# 02_TFT_LED.net
KiCad netlist of a schematic drawn in Altium Designer
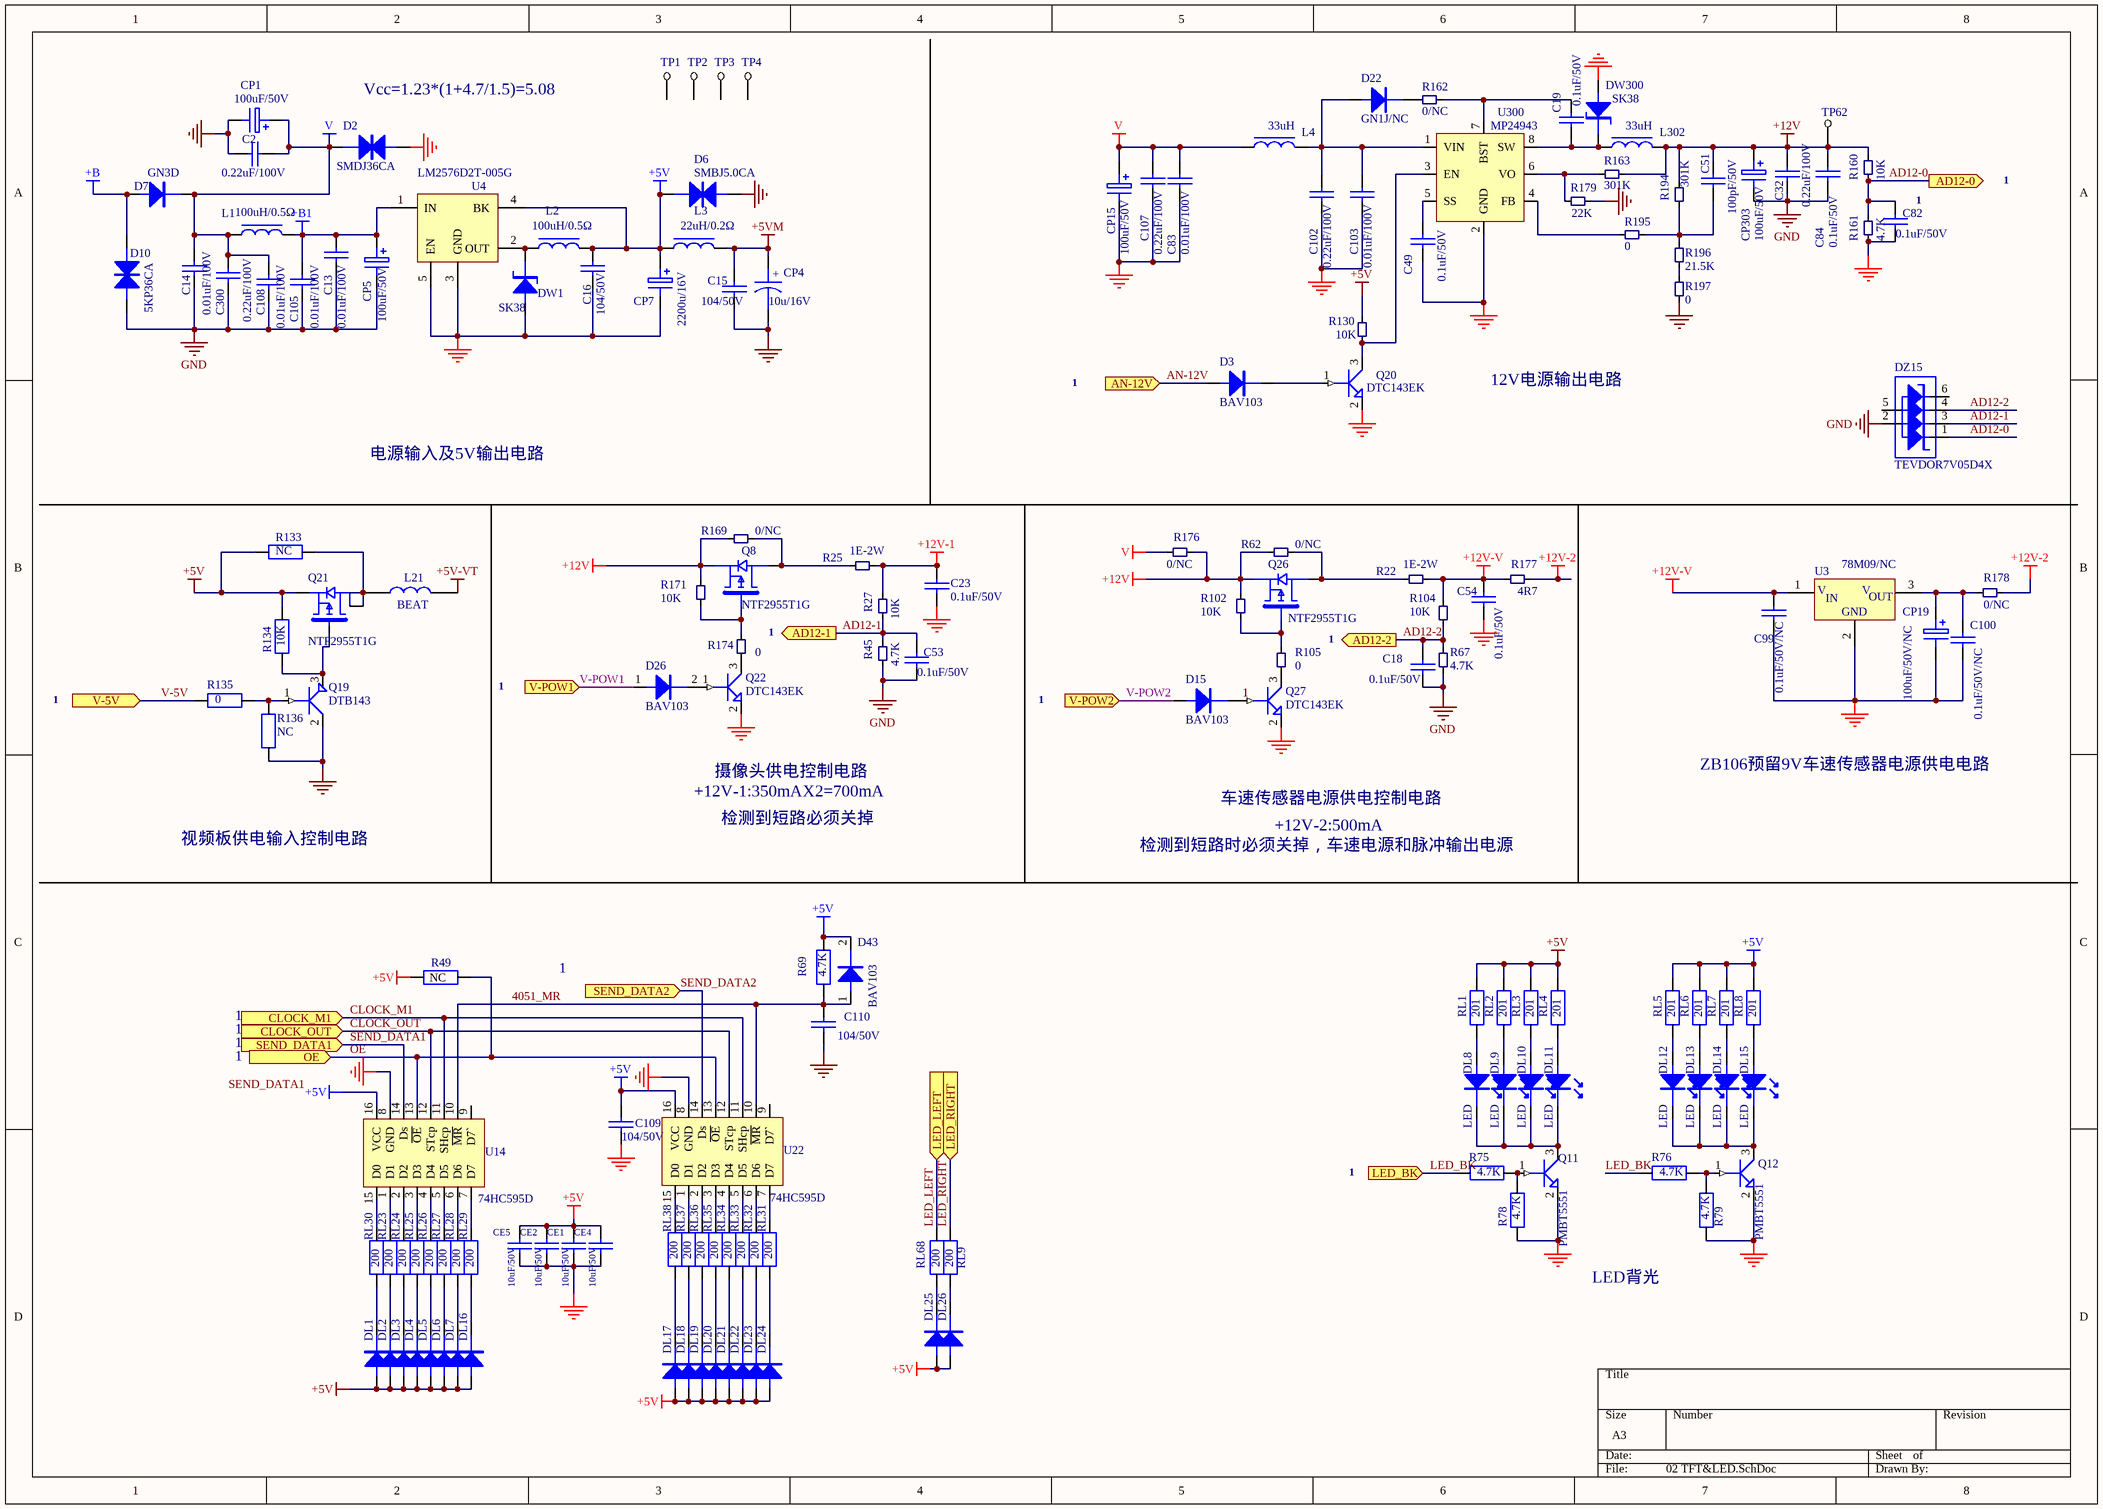
[diagram p0: 02 TFT&LED.SchDoc]

(export (version "E")
  (design (tool "Eeschema 10.0.6"))
  (components
    (comp (ref "C2")
      (value "0.22uF/100V")
      (footprint "CR1206")
      (description "Capacitor")
      (libsource (lib "*") (part "CAP"))
    )
    (comp (ref "C13")
      (value "0.01uF/100V")
      (footprint "CR0805")
      (description "Capacitor")
      (libsource (lib "*") (part "CAP"))
    )
    (comp (ref "C14")
      (value "0.01uF/100V")
      (footprint "CR0805")
      (description "Capacitor")
      (libsource (lib "*") (part "CAP"))
    )
    (comp (ref "C15")
      (value "104/50V")
      (footprint "CR0805")
      (description "Capacitor")
      (libsource (lib "*") (part "CAP"))
    )
    (comp (ref "C16")
      (value "104/50V")
      (footprint "CR0805")
      (description "Capacitor")
      (libsource (lib "*") (part "CAP"))
    )
    (comp (ref "C18")
      (value "0.1uF/50V")
      (footprint "CR0805")
      (description "Capacitor")
      (libsource (lib "*") (part "CAP"))
    )
    (comp (ref "C19")
      (value "0.1uF/50V")
      (footprint "CR0805")
      (description "Capacitor")
      (libsource (lib "*") (part "CAP"))
    )
    (comp (ref "C23")
      (value "0.1uF/50V")
      (footprint "CR0805")
      (description "Capacitor")
      (libsource (lib "*") (part "CAP"))
    )
    (comp (ref "C32")
      (value "0.22uF/100V")
      (footprint "CR1206")
      (description "Capacitor")
      (libsource (lib "*") (part "CAP"))
    )
    (comp (ref "C49")
      (value "0.1uF/50V")
      (footprint "CR0805")
      (description "Capacitor")
      (libsource (lib "*") (part "CAP"))
    )
    (comp (ref "C51")
      (value "100pF/50V")
      (footprint "CR0805")
      (description "Capacitor")
      (libsource (lib "*") (part "CAP"))
    )
    (comp (ref "C53")
      (value "0.1uF/50V")
      (footprint "CR0805")
      (description "Capacitor")
      (libsource (lib "*") (part "CAP"))
    )
    (comp (ref "C54")
      (value "0.1uF/50V")
      (footprint "CR0805")
      (description "Capacitor")
      (libsource (lib "*") (part "CAP"))
    )
    (comp (ref "C82")
      (value "0.1uF/50V")
      (footprint "CR0805")
      (description "Capacitor")
      (libsource (lib "*") (part "CAP"))
    )
    (comp (ref "C83")
      (value "0.01uF/100V")
      (footprint "CR0805")
      (description "Capacitor")
      (libsource (lib "*") (part "CAP"))
    )
    (comp (ref "C84")
      (value "0.1uF/50V")
      (footprint "CR0805")
      (description "Capacitor")
      (libsource (lib "*") (part "CAP"))
    )
    (comp (ref "C99")
      (value "0.1uF/50V/NC")
      (footprint "CR0805")
      (description "Capacitor")
      (libsource (lib "*") (part "CAP"))
    )
    (comp (ref "C100")
      (value "0.1uF/50V/NC")
      (footprint "CR0805")
      (description "Capacitor")
      (libsource (lib "*") (part "CAP"))
    )
    (comp (ref "C102")
      (value "0.22uF/100V")
      (footprint "CR1206")
      (description "Capacitor")
      (libsource (lib "*") (part "CAP"))
    )
    (comp (ref "C103")
      (value "0.01uF/100V")
      (footprint "CR0805")
      (description "Capacitor")
      (libsource (lib "*") (part "CAP"))
    )
    (comp (ref "C105")
      (value "0.01uF/100V")
      (footprint "CR0805")
      (description "Capacitor")
      (libsource (lib "*") (part "CAP"))
    )
    (comp (ref "C107")
      (value "0.22uF/100V")
      (footprint "CR1206")
      (description "Capacitor")
      (libsource (lib "*") (part "CAP"))
    )
    (comp (ref "C108")
      (value "0.01uF/100V")
      (footprint "CR0805")
      (description "Capacitor")
      (libsource (lib "*") (part "CAP"))
    )
    (comp (ref "C109")
      (value "104/50V")
      (footprint "CR0805")
      (description "Capacitor")
      (libsource (lib "*") (part "CAP"))
    )
    (comp (ref "C110")
      (value "104/50V")
      (footprint "CR0805")
      (description "Capacitor")
      (libsource (lib "*") (part "CAP"))
    )
    (comp (ref "C300")
      (value "0.22uF/100V")
      (footprint "CR1206")
      (description "Capacitor")
      (libsource (lib "*") (part "CAP"))
    )
    (comp (ref "CE1")
      (value "10uF/50V")
      (footprint "CR1206")
      (description "Capacitor")
      (libsource (lib "*") (part "CAP"))
    )
    (comp (ref "CE2")
      (value "10uF/50V")
      (footprint "CR1206")
      (description "Capacitor")
      (libsource (lib "*") (part "CAP"))
    )
    (comp (ref "CE4")
      (value "10uF/50V")
      (footprint "CR1206")
      (description "Capacitor")
      (libsource (lib "*") (part "CAP"))
    )
    (comp (ref "CE5")
      (value "10uF/50V")
      (footprint "CR1206")
      (description "Capacitor")
      (libsource (lib "*") (part "CAP"))
    )
    (comp (ref "CP1")
      (value "100uF/50V")
      (footprint "RB10")
      (description "电解电容")
      (libsource (lib "*") (part "ELECTRO1"))
    )
    (comp (ref "CP4")
      (value "10u/16V")
      (footprint "CE1206")
      (description "Capacitor")
      (libsource (lib "*") (part "CAPACITOR POL"))
    )
    (comp (ref "CP5")
      (value "100uF/50V")
      (footprint "RB5-1")
      (description "电解电容")
      (libsource (lib "*") (part "ELECTRO1"))
    )
    (comp (ref "CP7")
      (value "2200u/16V")
      (footprint "RB12.5")
      (description "电解电容")
      (libsource (lib "*") (part "ELECTRO1"))
    )
    (comp (ref "CP15")
      (value "100uF/50V")
      (footprint "RB5-1")
      (description "电解电容")
      (libsource (lib "*") (part "ELECTRO1"))
    )
    (comp (ref "CP19")
      (value "100uF/50V/NC")
      (footprint "RB5-1")
      (description "电解电容")
      (libsource (lib "*") (part "ELECTRO1"))
    )
    (comp (ref "CP303")
      (value "100uF/50V")
      (footprint "RB5-1")
      (description "电解电容")
      (libsource (lib "*") (part "ELECTRO1"))
    )
    (comp (ref "D2") (value "SMDJ36CA") (footprint "SMC-D") (libsource (lib "YDM-SQ-1SCH") (part "TVS")))
    (comp (ref "D3")
      (value "BAV103")
      (footprint "SOD-80C")
      (description "二极管")
      (libsource (lib "") (part "DIODE_1"))
    )
    (comp (ref "D6") (value "SMBJ5.0CA") (footprint "SMB-D") (libsource (lib "YDM-SQ-1SCH") (part "TVS")))
    (comp (ref "D7")
      (value "GN3D")
      (footprint "SMC")
      (description "二极管")
      (libsource (lib "") (part "DIODE_1"))
    )
    (comp (ref "D10") (value "5KP36CA") (footprint "D-17") (libsource (lib "*") (part "TVS")))
    (comp (ref "D15")
      (value "BAV103")
      (footprint "SOD-80C")
      (description "二极管")
      (libsource (lib "") (part "DIODE_1"))
    )
    (comp (ref "D22")
      (value "GN1J/NC")
      (footprint "SMA")
      (description "二极管")
      (libsource (lib "") (part "DIODE_1"))
    )
    (comp (ref "D26")
      (value "BAV103")
      (footprint "SOD-80C")
      (description "二极管")
      (libsource (lib "*") (part "DIODE"))
    )
    (comp (ref "D43")
      (value "BAV103")
      (footprint "SOD-80C")
      (description "二极管")
      (libsource (lib "*") (part "DIODE"))
    )
    (comp (ref "DL1")
      (value "~")
      (footprint "LED1210")
      (description "贴片二极管")
      (libsource (lib "*") (part "DOS"))
    )
    (comp (ref "DL2")
      (value "~")
      (footprint "LED1210")
      (description "贴片二极管")
      (libsource (lib "*") (part "DOS"))
    )
    (comp (ref "DL3")
      (value "~")
      (footprint "LED1210")
      (description "贴片二极管")
      (libsource (lib "*") (part "DOS"))
    )
    (comp (ref "DL4")
      (value "~")
      (footprint "LED1210")
      (description "贴片二极管")
      (libsource (lib "*") (part "DOS"))
    )
    (comp (ref "DL5")
      (value "~")
      (footprint "LED1210")
      (description "贴片二极管")
      (libsource (lib "*") (part "DOS"))
    )
    (comp (ref "DL6")
      (value "~")
      (footprint "LED1210")
      (description "贴片二极管")
      (libsource (lib "*") (part "DOS"))
    )
    (comp (ref "DL7")
      (value "~")
      (footprint "LED1210")
      (description "贴片二极管")
      (libsource (lib "*") (part "DOS"))
    )
    (comp (ref "DL8")
      (value "LED")
      (footprint "LED1210")
      (description "贴片LED")
      (libsource (lib "*") (part "LED"))
    )
    (comp (ref "DL9")
      (value "LED")
      (footprint "LED1210")
      (description "贴片LED")
      (libsource (lib "*") (part "LED"))
    )
    (comp (ref "DL10")
      (value "LED")
      (footprint "LED1210")
      (description "贴片LED")
      (libsource (lib "*") (part "LED"))
    )
    (comp (ref "DL11")
      (value "LED")
      (footprint "LED1210")
      (description "贴片LED")
      (libsource (lib "*") (part "LED"))
    )
    (comp (ref "DL12")
      (value "LED")
      (footprint "LED1210")
      (description "贴片LED")
      (libsource (lib "*") (part "LED"))
    )
    (comp (ref "DL13")
      (value "LED")
      (footprint "LED1210")
      (description "贴片LED")
      (libsource (lib "*") (part "LED"))
    )
    (comp (ref "DL14")
      (value "LED")
      (footprint "LED1210")
      (description "贴片LED")
      (libsource (lib "*") (part "LED"))
    )
    (comp (ref "DL15")
      (value "LED")
      (footprint "LED1210")
      (description "贴片LED")
      (libsource (lib "*") (part "LED"))
    )
    (comp (ref "DL16")
      (value "~")
      (footprint "LED1210")
      (description "贴片二极管")
      (libsource (lib "*") (part "DOS"))
    )
    (comp (ref "DL17")
      (value "~")
      (footprint "LED1210")
      (description "贴片二极管")
      (libsource (lib "*") (part "DOS"))
    )
    (comp (ref "DL18")
      (value "~")
      (footprint "LED1210")
      (description "贴片二极管")
      (libsource (lib "*") (part "DOS"))
    )
    (comp (ref "DL19")
      (value "~")
      (footprint "LED1210")
      (description "贴片二极管")
      (libsource (lib "*") (part "DOS"))
    )
    (comp (ref "DL20")
      (value "~")
      (footprint "LED1210")
      (description "贴片二极管")
      (libsource (lib "*") (part "DOS"))
    )
    (comp (ref "DL21")
      (value "~")
      (footprint "LED1210")
      (description "贴片二极管")
      (libsource (lib "*") (part "DOS"))
    )
    (comp (ref "DL22")
      (value "~")
      (footprint "LED1210")
      (description "贴片二极管")
      (libsource (lib "*") (part "DOS"))
    )
    (comp (ref "DL23")
      (value "~")
      (footprint "LED1210")
      (description "贴片二极管")
      (libsource (lib "*") (part "DOS"))
    )
    (comp (ref "DL24")
      (value "~")
      (footprint "LED1210")
      (description "贴片二极管")
      (libsource (lib "*") (part "DOS"))
    )
    (comp (ref "DL25")
      (value "~")
      (footprint "LED1210")
      (description "贴片二极管")
      (libsource (lib "*") (part "DOS"))
    )
    (comp (ref "DL26")
      (value "~")
      (footprint "LED1210")
      (description "贴片二极管")
      (libsource (lib "*") (part "DOS"))
    )
    (comp (ref "DW1")
      (value "SK38")
      (footprint "SMC")
      (description "稳压二极管")
      (libsource (lib "*") (part "DW"))
    )
    (comp (ref "DW300")
      (value "SK38")
      (footprint "SMC")
      (description "稳压二极管")
      (libsource (lib "*") (part "DW"))
    )
    (comp (ref "DZ15")
      (value "TEVDOR7V05D4X")
      (footprint "SOT-457")
      (description "二极管排")
      (libsource (lib "yibiaoschlib") (part "TEVDOR7V05D4X"))
    )
    (comp (ref "L1")
      (value "100uH/0.5Ω")
      (footprint "Ind-R13-7-100")
      (description "电感")
      (libsource (lib "*") (part "L"))
    )
    (comp (ref "L2")
      (value "100uH/0.5Ω")
      (footprint "Ind-R13-7-100")
      (description "电感")
      (libsource (lib "*") (part "L"))
    )
    (comp (ref "L3")
      (value "22uH/0.2Ω")
      (footprint "SS0603")
      (description "SS0603220ML")
      (libsource (lib "*") (part "L"))
    )
    (comp (ref "L4")
      (value "33uH")
      (footprint "Ind-R13-7-100")
      (description "电感")
      (libsource (lib "*") (part "L"))
    )
    (comp (ref "L21") (value "BEAT") (footprint "CR0805") (libsource (lib "YDM-SQ-1SCH") (part "BEAT")))
    (comp (ref "L302")
      (value "33uH")
      (footprint "Ind-R13-7-100")
      (description "电感")
      (libsource (lib "*") (part "L"))
    )
    (comp (ref "Q8")
      (value "NTF2955T1G")
      (footprint "SOT-223")
      (description "MOS")
      (libsource (lib "Ô­ÀíÍ¼¿â-1SCH") (part "MOS-P"))
    )
    (comp (ref "Q11")
      (value "PMBT5551")
      (footprint "SOT23")
      (description "PNP   三极管")
      (libsource (lib "Ô­ÀíÍ¼¿â-1SCH") (part "PMBT5551"))
    )
    (comp (ref "Q12")
      (value "PMBT5551")
      (footprint "SOT23")
      (description "PNP   三极管")
      (libsource (lib "Ô­ÀíÍ¼¿â-1SCH") (part "PMBT5551"))
    )
    (comp (ref "Q19") (value "DTB143") (footprint "SOT23") (libsource (lib "Ô­ÀíÍ¼¿â-1SCH") (part "BCX53")))
    (comp (ref "Q20")
      (value "DTC143EK")
      (footprint "SOT23")
      (description "NPN")
      (libsource (lib "Ô­ÀíÍ¼¿â-1SCH") (part "DTC143"))
    )
    (comp (ref "Q21")
      (value "NTF2955T1G")
      (footprint "SOT-223")
      (description "MOS")
      (libsource (lib "yibiaoschlib") (part "NTF2955T1G"))
    )
    (comp (ref "Q22")
      (value "DTC143EK")
      (footprint "SOT23")
      (description "NPN")
      (libsource (lib "Ô­ÀíÍ¼¿â-1SCH") (part "DTC143"))
    )
    (comp (ref "Q26")
      (value "NTF2955T1G")
      (footprint "SOT-223")
      (description "MOS")
      (libsource (lib "Ô­ÀíÍ¼¿â-1SCH") (part "MOS-P"))
    )
    (comp (ref "Q27")
      (value "DTC143EK")
      (footprint "SOT23")
      (description "NPN")
      (libsource (lib "Ô­ÀíÍ¼¿â-1SCH") (part "DTC143"))
    )
    (comp (ref "R22")
      (value "1E-2W")
      (footprint "R2512")
      (description "贴片电阻")
      (libsource (lib "YDM-SQ-1SCH") (part "Resister mini"))
    )
    (comp (ref "R25")
      (value "1E-2W")
      (footprint "R2512")
      (description "贴片电阻")
      (libsource (lib "YDM-SQ-1SCH") (part "Resister mini"))
    )
    (comp (ref "R27")
      (value "10K")
      (footprint "CR0805")
      (description "贴片电阻")
      (libsource (lib "YDM-SQ-1SCH") (part "Resister mini"))
    )
    (comp (ref "R45")
      (value "4.7K")
      (footprint "CR0805")
      (description "贴片电阻")
      (libsource (lib "YDM-SQ-1SCH") (part "Resister mini"))
    )
    (comp (ref "R49")
      (value "NC")
      (footprint "CR0805")
      (description "贴片电阻")
      (libsource (lib "*") (part "RES"))
    )
    (comp (ref "R62")
      (value "0/NC")
      (footprint "CR1206")
      (description "贴片电阻")
      (libsource (lib "YDM-SQ-1SCH") (part "Resister mini"))
    )
    (comp (ref "R67")
      (value "4.7K")
      (footprint "CR0805")
      (description "贴片电阻")
      (libsource (lib "YDM-SQ-1SCH") (part "Resister mini"))
    )
    (comp (ref "R69")
      (value "4.7K")
      (footprint "CR0805")
      (description "贴片电阻")
      (libsource (lib "*") (part "RES"))
    )
    (comp (ref "R75")
      (value "4.7K")
      (footprint "CR0805")
      (description "贴片电阻")
      (libsource (lib "YDM-SQ-1SCH") (part "RES"))
    )
    (comp (ref "R76")
      (value "4.7K")
      (footprint "CR0805")
      (description "贴片电阻")
      (libsource (lib "YDM-SQ-1SCH") (part "RES"))
    )
    (comp (ref "R78")
      (value "4.7K")
      (footprint "CR0805")
      (description "贴片电阻")
      (libsource (lib "YDM-SQ-1SCH") (part "RES"))
    )
    (comp (ref "R79")
      (value "4.7K")
      (footprint "CR0805")
      (description "贴片电阻")
      (libsource (lib "YDM-SQ-1SCH") (part "RES"))
    )
    (comp (ref "R102")
      (value "10K")
      (footprint "CR0805")
      (description "贴片电阻")
      (libsource (lib "YDM-SQ-1SCH") (part "Resister mini"))
    )
    (comp (ref "R104")
      (value "10K")
      (footprint "CR0805")
      (description "贴片电阻")
      (libsource (lib "YDM-SQ-1SCH") (part "Resister mini"))
    )
    (comp (ref "R105")
      (value "0")
      (footprint "CR0805")
      (description "贴片电阻")
      (libsource (lib "YDM-SQ-1SCH") (part "Resister mini"))
    )
    (comp (ref "R130")
      (value "10K")
      (footprint "CR0805")
      (description "贴片电阻")
      (libsource (lib "YDM-SQ-1SCH") (part "Resister mini"))
    )
    (comp (ref "R133")
      (value "NC")
      (footprint "CR1206")
      (description "贴片电阻")
      (libsource (lib "YDM-SQ-1SCH") (part "RES"))
    )
    (comp (ref "R134")
      (value "10K")
      (footprint "CR0805")
      (description "贴片电阻")
      (libsource (lib "YDM-SQ-1SCH") (part "RES"))
    )
    (comp (ref "R135")
      (value "0")
      (footprint "CR0805")
      (description "贴片电阻")
      (libsource (lib "YDM-SQ-1SCH") (part "RES"))
    )
    (comp (ref "R136")
      (value "NC")
      (footprint "CR0805")
      (description "贴片电阻")
      (libsource (lib "YDM-SQ-1SCH") (part "RES"))
    )
    (comp (ref "R160")
      (value "10K")
      (footprint "CR0805")
      (description "贴片电阻")
      (libsource (lib "YDM-SQ-1SCH") (part "Resister mini"))
    )
    (comp (ref "R161")
      (value "4.7K")
      (footprint "CR0805")
      (description "贴片电阻")
      (libsource (lib "YDM-SQ-1SCH") (part "Resister mini"))
    )
    (comp (ref "R162")
      (value "0/NC")
      (footprint "CR0805")
      (description "贴片电阻")
      (libsource (lib "YDM-SQ-1SCH") (part "Resister mini"))
    )
    (comp (ref "R163")
      (value "301K")
      (footprint "CR0805")
      (description "贴片电阻")
      (libsource (lib "YDM-SQ-1SCH") (part "Resister mini"))
    )
    (comp (ref "R169")
      (value "0/NC")
      (footprint "CR1206")
      (description "贴片电阻")
      (libsource (lib "YDM-SQ-1SCH") (part "Resister mini"))
    )
    (comp (ref "R171")
      (value "10K")
      (footprint "CR0805")
      (description "贴片电阻")
      (libsource (lib "YDM-SQ-1SCH") (part "Resister mini"))
    )
    (comp (ref "R174")
      (value "0")
      (footprint "CR0805")
      (description "贴片电阻")
      (libsource (lib "YDM-SQ-1SCH") (part "Resister mini"))
    )
    (comp (ref "R176")
      (value "0/NC")
      (footprint "CR1206")
      (description "贴片电阻")
      (libsource (lib "YDM-SQ-1SCH") (part "Resister mini"))
    )
    (comp (ref "R177")
      (value "4R7")
      (footprint "CR1206")
      (description "贴片电阻")
      (libsource (lib "YDM-SQ-1SCH") (part "Resister mini"))
    )
    (comp (ref "R178")
      (value "0/NC")
      (footprint "CR1206")
      (description "贴片电阻")
      (libsource (lib "YDM-SQ-1SCH") (part "Resister mini"))
    )
    (comp (ref "R179")
      (value "22K")
      (footprint "CR0805")
      (description "贴片电阻")
      (libsource (lib "YDM-SQ-1SCH") (part "Resister mini"))
    )
    (comp (ref "R194")
      (value "301K")
      (footprint "CR0805")
      (description "贴片电阻")
      (libsource (lib "YDM-SQ-1SCH") (part "Resister mini"))
    )
    (comp (ref "R195")
      (value "0")
      (footprint "CR0805")
      (description "贴片电阻")
      (libsource (lib "YDM-SQ-1SCH") (part "Resister mini"))
    )
    (comp (ref "R196")
      (value "21.5K")
      (footprint "CR0805")
      (description "贴片电阻")
      (libsource (lib "YDM-SQ-1SCH") (part "Resister mini"))
    )
    (comp (ref "R197")
      (value "0")
      (footprint "CR0805")
      (description "贴片电阻")
      (libsource (lib "YDM-SQ-1SCH") (part "Resister mini"))
    )
    (comp (ref "RL1")
      (value "201")
      (footprint "CR0805")
      (description "贴片电阻")
      (libsource (lib "*") (part "RES"))
    )
    (comp (ref "RL2")
      (value "201")
      (footprint "CR0805")
      (description "贴片电阻")
      (libsource (lib "*") (part "RES"))
    )
    (comp (ref "RL3")
      (value "201")
      (footprint "CR0805")
      (description "贴片电阻")
      (libsource (lib "*") (part "RES"))
    )
    (comp (ref "RL4")
      (value "201")
      (footprint "CR0805")
      (description "贴片电阻")
      (libsource (lib "*") (part "RES"))
    )
    (comp (ref "RL5")
      (value "201")
      (footprint "CR0805")
      (description "贴片电阻")
      (libsource (lib "*") (part "RES"))
    )
    (comp (ref "RL6")
      (value "201")
      (footprint "CR0805")
      (description "贴片电阻")
      (libsource (lib "*") (part "RES"))
    )
    (comp (ref "RL7")
      (value "201")
      (footprint "CR0805")
      (description "贴片电阻")
      (libsource (lib "*") (part "RES"))
    )
    (comp (ref "RL8")
      (value "201")
      (footprint "CR0805")
      (description "贴片电阻")
      (libsource (lib "*") (part "RES"))
    )
    (comp (ref "RL9")
      (value "200")
      (footprint "CR0805")
      (description "贴片电阻")
      (libsource (lib "*") (part "RES"))
    )
    (comp (ref "RL23")
      (value "200")
      (footprint "CR0805")
      (description "贴片电阻")
      (libsource (lib "*") (part "RES"))
    )
    (comp (ref "RL24")
      (value "200")
      (footprint "CR0805")
      (description "贴片电阻")
      (libsource (lib "*") (part "RES"))
    )
    (comp (ref "RL25")
      (value "200")
      (footprint "CR0805")
      (description "贴片电阻")
      (libsource (lib "*") (part "RES"))
    )
    (comp (ref "RL26")
      (value "200")
      (footprint "CR0805")
      (description "贴片电阻")
      (libsource (lib "*") (part "RES"))
    )
    (comp (ref "RL27")
      (value "200")
      (footprint "CR0805")
      (description "贴片电阻")
      (libsource (lib "*") (part "RES"))
    )
    (comp (ref "RL28")
      (value "200")
      (footprint "CR0805")
      (description "贴片电阻")
      (libsource (lib "*") (part "RES"))
    )
    (comp (ref "RL29")
      (value "200")
      (footprint "CR0805")
      (description "贴片电阻")
      (libsource (lib "*") (part "RES"))
    )
    (comp (ref "RL30")
      (value "200")
      (footprint "CR0805")
      (description "贴片电阻")
      (libsource (lib "*") (part "RES"))
    )
    (comp (ref "RL31")
      (value "200")
      (footprint "CR0805")
      (description "贴片电阻")
      (libsource (lib "*") (part "RES"))
    )
    (comp (ref "RL32")
      (value "200")
      (footprint "CR0805")
      (description "贴片电阻")
      (libsource (lib "*") (part "RES"))
    )
    (comp (ref "RL33")
      (value "200")
      (footprint "CR0805")
      (description "贴片电阻")
      (libsource (lib "*") (part "RES"))
    )
    (comp (ref "RL34")
      (value "200")
      (footprint "CR0805")
      (description "贴片电阻")
      (libsource (lib "*") (part "RES"))
    )
    (comp (ref "RL35")
      (value "200")
      (footprint "CR0805")
      (description "贴片电阻")
      (libsource (lib "*") (part "RES"))
    )
    (comp (ref "RL36")
      (value "200")
      (footprint "CR0805")
      (description "贴片电阻")
      (libsource (lib "*") (part "RES"))
    )
    (comp (ref "RL37")
      (value "200")
      (footprint "CR0805")
      (description "贴片电阻")
      (libsource (lib "*") (part "RES"))
    )
    (comp (ref "RL38")
      (value "200")
      (footprint "CR0805")
      (description "贴片电阻")
      (libsource (lib "*") (part "RES"))
    )
    (comp (ref "RL68")
      (value "200")
      (footprint "CR0805")
      (description "贴片电阻")
      (libsource (lib "*") (part "RES"))
    )
    (comp (ref "TP1") (value "TP") (footprint "MARK") (libsource (lib "YDM-SQ-1SCH") (part "TP")))
    (comp (ref "TP2") (value "TP") (footprint "MARK") (libsource (lib "YDM-SQ-1SCH") (part "TP")))
    (comp (ref "TP3") (value "TP") (footprint "MARK") (libsource (lib "YDM-SQ-1SCH") (part "TP")))
    (comp (ref "TP4") (value "TP") (footprint "MARK") (libsource (lib "YDM-SQ-1SCH") (part "TP")))
    (comp (ref "TP62") (value "~") (footprint "TP") (libsource (lib "YDM-SQ-1SCH") (part "TP")))
    (comp (ref "U3")
      (value "78M09/NC")
      (footprint "DPAK")
      (description "IC-三端稳压")
      (libsource (lib "HNS-SCH") (part "78M12"))
    )
    (comp (ref "U4")
      (value "LM2576D2T-005G")
      (footprint "SOT-263-5")
      (description "DC/DC")
      (libsource (lib "*") (part "LDO_1"))
    )
    (comp (ref "U14") (value "74HC595D") (footprint "SO-16") (libsource (lib "*") (part "74HC595D")))
    (comp (ref "U22") (value "74HC595D") (footprint "SO-16") (libsource (lib "*") (part "74HC595D")))
    (comp (ref "U300")
      (value "MP24943")
      (footprint "SOIC8E")
      (description "IC-CAN DRIVER")
      (libsource (lib "Ô­ÀíÍ¼¿â-1SCH") (part "MP24943"))
    )
  )
  (nets
    (net (code "1") (name "+5V") (class "Default")
      (node (ref "C109") (pin "2") (pinfunction "2_2") (pintype "passive"))
      (node (ref "C16") (pin "2") (pinfunction "2_2") (pintype "passive"))
      (node (ref "CE1") (pin "1") (pinfunction "1_1") (pintype "passive"))
      (node (ref "CE2") (pin "1") (pinfunction "1_1") (pintype "passive"))
      (node (ref "CE4") (pin "1") (pinfunction "1_1") (pintype "passive"))
      (node (ref "CE5") (pin "1") (pinfunction "1_1") (pintype "passive"))
      (node (ref "CP7") (pin "1") (pinfunction "1_1") (pintype "passive"))
      (node (ref "D43") (pin "2") (pinfunction "K_2") (pintype "passive"))
      (node (ref "D6") (pin "1") (pinfunction "1_1") (pintype "passive"))
      (node (ref "DL1") (pin "1") (pinfunction "A_1") (pintype "passive"))
      (node (ref "DL16") (pin "1") (pinfunction "A_1") (pintype "passive"))
      (node (ref "DL17") (pin "1") (pinfunction "A_1") (pintype "passive"))
      (node (ref "DL18") (pin "1") (pinfunction "A_1") (pintype "passive"))
      (node (ref "DL19") (pin "1") (pinfunction "A_1") (pintype "passive"))
      (node (ref "DL2") (pin "1") (pinfunction "A_1") (pintype "passive"))
      (node (ref "DL20") (pin "1") (pinfunction "A_1") (pintype "passive"))
      (node (ref "DL21") (pin "1") (pinfunction "A_1") (pintype "passive"))
      (node (ref "DL22") (pin "1") (pinfunction "A_1") (pintype "passive"))
      (node (ref "DL23") (pin "1") (pinfunction "A_1") (pintype "passive"))
      (node (ref "DL24") (pin "1") (pinfunction "A_1") (pintype "passive"))
      (node (ref "DL25") (pin "1") (pinfunction "A_1") (pintype "passive"))
      (node (ref "DL26") (pin "1") (pinfunction "A_1") (pintype "passive"))
      (node (ref "DL3") (pin "1") (pinfunction "A_1") (pintype "passive"))
      (node (ref "DL4") (pin "1") (pinfunction "A_1") (pintype "passive"))
      (node (ref "DL5") (pin "1") (pinfunction "A_1") (pintype "passive"))
      (node (ref "DL6") (pin "1") (pinfunction "A_1") (pintype "passive"))
      (node (ref "DL7") (pin "1") (pinfunction "A_1") (pintype "passive"))
      (node (ref "L2") (pin "2") (pinfunction "2_2") (pintype "passive"))
      (node (ref "L3") (pin "1") (pinfunction "1_1") (pintype "passive"))
      (node (ref "Q21") (pin "3") (pinfunction "S_3") (pintype "passive"))
      (node (ref "R130") (pin "1") (pinfunction "1_1") (pintype "passive"))
      (node (ref "R133") (pin "1") (pinfunction "1_1") (pintype "passive"))
      (node (ref "R134") (pin "1") (pinfunction "1_1") (pintype "passive"))
      (node (ref "R49") (pin "1") (pinfunction "1_1") (pintype "passive"))
      (node (ref "R69") (pin "2") (pinfunction "2_2") (pintype "passive"))
      (node (ref "RL1") (pin "1") (pinfunction "1_1") (pintype "passive"))
      (node (ref "RL2") (pin "1") (pinfunction "1_1") (pintype "passive"))
      (node (ref "RL3") (pin "1") (pinfunction "1_1") (pintype "passive"))
      (node (ref "RL4") (pin "1") (pinfunction "1_1") (pintype "passive"))
      (node (ref "RL5") (pin "1") (pinfunction "1_1") (pintype "passive"))
      (node (ref "RL6") (pin "1") (pinfunction "1_1") (pintype "passive"))
      (node (ref "RL7") (pin "1") (pinfunction "1_1") (pintype "passive"))
      (node (ref "RL8") (pin "1") (pinfunction "1_1") (pintype "passive"))
      (node (ref "U14") (pin "16") (pinfunction "VCC_16") (pintype "passive"))
      (node (ref "U22") (pin "16") (pinfunction "VCC_16") (pintype "passive"))
      (node (ref "U4") (pin "4") (pinfunction "BK_4") (pintype "passive"))
    )
    (net (code "2") (name "+5V-VT") (class "Default")
      (node (ref "L21") (pin "2") (pinfunction "2_2") (pintype "passive"))
    )
    (net (code "3") (name "+5VM") (class "Default")
      (node (ref "C15") (pin "1") (pinfunction "1_1") (pintype "passive"))
      (node (ref "CP4") (pin "1") (pinfunction "1_1") (pintype "passive"))
      (node (ref "L3") (pin "2") (pinfunction "2_2") (pintype "passive"))
    )
    (net (code "4") (name "+12V") (class "Default")
      (node (ref "C32") (pin "2") (pinfunction "2_2") (pintype "passive"))
      (node (ref "C51") (pin "2") (pinfunction "2_2") (pintype "passive"))
      (node (ref "C84") (pin "2") (pinfunction "2_2") (pintype "passive"))
      (node (ref "CP303") (pin "1") (pinfunction "1_1") (pintype "passive"))
      (node (ref "L302") (pin "2") (pinfunction "2_2") (pintype "passive"))
      (node (ref "Q26") (pin "3") (pintype "passive"))
      (node (ref "Q8") (pin "3") (pintype "passive"))
      (node (ref "R102") (pin "2") (pinfunction "2_2") (pintype "passive"))
      (node (ref "R160") (pin "2") (pinfunction "2_2") (pintype "passive"))
      (node (ref "R163") (pin "2") (pinfunction "2_2") (pintype "passive"))
      (node (ref "R169") (pin "1") (pinfunction "1_1") (pintype "passive"))
      (node (ref "R171") (pin "2") (pinfunction "2_2") (pintype "passive"))
      (node (ref "R176") (pin "2") (pinfunction "2_2") (pintype "passive"))
      (node (ref "R194") (pin "1") (pinfunction "1_1") (pintype "passive"))
      (node (ref "R62") (pin "1") (pinfunction "1_1") (pintype "passive"))
      (node (ref "TP62") (pin "1") (pinfunction "1_1") (pintype "passive"))
    )
    (net (code "5") (name "+12V-1") (class "Default")
      (node (ref "C23") (pin "1") (pinfunction "1_1") (pintype "passive"))
      (node (ref "R25") (pin "2") (pinfunction "2_2") (pintype "passive"))
      (node (ref "R27") (pin "2") (pinfunction "2_2") (pintype "passive"))
    )
    (net (code "6") (name "+12V-2") (class "Default")
      (node (ref "R177") (pin "2") (pinfunction "2_2") (pintype "passive"))
      (node (ref "R178") (pin "2") (pinfunction "2_2") (pintype "passive"))
    )
    (net (code "7") (name "+12V-V") (class "Default")
      (node (ref "C54") (pin "1") (pinfunction "1_1") (pintype "passive"))
      (node (ref "C99") (pin "2") (pinfunction "2_2") (pintype "passive"))
      (node (ref "R104") (pin "2") (pinfunction "2_2") (pintype "passive"))
      (node (ref "R177") (pin "1") (pinfunction "1_1") (pintype "passive"))
      (node (ref "R22") (pin "2") (pinfunction "2_2") (pintype "passive"))
      (node (ref "U3") (pin "1") (pinfunction "VIN_1") (pintype "passive"))
    )
    (net (code "8") (name "+B") (class "Default")
      (node (ref "D10") (pin "1") (pinfunction "1_1") (pintype "passive"))
      (node (ref "D7") (pin "1") (pinfunction "A_1") (pintype "passive"))
    )
    (net (code "9") (name "+B1") (class "Default")
      (node (ref "C105") (pin "2") (pinfunction "2_2") (pintype "passive"))
      (node (ref "C13") (pin "2") (pinfunction "2_2") (pintype "passive"))
      (node (ref "CP5") (pin "1") (pinfunction "1_1") (pintype "passive"))
      (node (ref "L1") (pin "2") (pinfunction "2_2") (pintype "passive"))
      (node (ref "U4") (pin "1") (pinfunction "IN_1") (pintype "passive"))
    )
    (net (code "10") (name "/4051_MR") (class "Default")
      (node (ref "C110") (pin "1") (pinfunction "1_1") (pintype "passive"))
      (node (ref "D43") (pin "1") (pinfunction "A_1") (pintype "passive"))
      (node (ref "R69") (pin "1") (pinfunction "1_1") (pintype "passive"))
      (node (ref "U14") (pin "10") (pinfunction "~{MR}_10") (pintype "passive"))
      (node (ref "U22") (pin "10") (pinfunction "~{MR}_10") (pintype "passive"))
    )
    (net (code "11") (name "/AD12-0") (class "Default")
      (node (ref "C82") (pin "2") (pinfunction "2_2") (pintype "passive"))
      (node (ref "DZ15") (pin "1") (pintype "passive"))
      (node (ref "R160") (pin "1") (pinfunction "1_1") (pintype "passive"))
      (node (ref "R161") (pin "2") (pinfunction "2_2") (pintype "passive"))
    )
    (net (code "12") (name "/AD12-1") (class "Default")
      (node (ref "C53") (pin "2") (pinfunction "2_2") (pintype "passive"))
      (node (ref "DZ15") (pin "3") (pintype "passive"))
      (node (ref "R27") (pin "1") (pinfunction "1_1") (pintype "passive"))
      (node (ref "R45") (pin "2") (pinfunction "2_2") (pintype "passive"))
    )
    (net (code "13") (name "/AD12-2") (class "Default")
      (node (ref "C18") (pin "2") (pinfunction "2_2") (pintype "passive"))
      (node (ref "DZ15") (pin "4") (pintype "passive"))
      (node (ref "R104") (pin "1") (pinfunction "1_1") (pintype "passive"))
      (node (ref "R67") (pin "2") (pinfunction "2_2") (pintype "passive"))
    )
    (net (code "14") (name "/AN-12V") (class "Default")
      (node (ref "D3") (pin "1") (pinfunction "A_1") (pintype "passive"))
    )
    (net (code "15") (name "/CLOCK_M1") (class "Default")
      (node (ref "U14") (pin "11") (pinfunction "SHcp_11") (pintype "passive"))
      (node (ref "U22") (pin "11") (pinfunction "SHcp_11") (pintype "passive"))
    )
    (net (code "16") (name "/CLOCK_OUT") (class "Default")
      (node (ref "U14") (pin "12") (pinfunction "STcp_12") (pintype "passive"))
      (node (ref "U22") (pin "12") (pinfunction "STcp_12") (pintype "passive"))
    )
    (net (code "17") (name "/LED_BK") (class "Default")
      (node (ref "R75") (pin "1") (pinfunction "1_1") (pintype "passive"))
      (node (ref "R76") (pin "1") (pinfunction "1_1") (pintype "passive"))
    )
    (net (code "18") (name "/LED_LEFT") (class "Default")
      (node (ref "RL68") (pin "1") (pinfunction "1_1") (pintype "passive"))
    )
    (net (code "19") (name "/LED_RIGHT") (class "Default")
      (node (ref "RL9") (pin "1") (pinfunction "1_1") (pintype "passive"))
    )
    (net (code "20") (name "/OE") (class "Default")
      (node (ref "R49") (pin "2") (pinfunction "2_2") (pintype "passive"))
      (node (ref "U14") (pin "13") (pinfunction "~{OE}_13") (pintype "passive"))
      (node (ref "U22") (pin "13") (pinfunction "~{OE}_13") (pintype "passive"))
    )
    (net (code "21") (name "/SEND_DATA1") (class "Default")
      (node (ref "U14") (pin "14") (pinfunction "Ds_14") (pintype "passive"))
    )
    (net (code "22") (name "/SEND_DATA2") (class "Default")
      (node (ref "U22") (pin "14") (pinfunction "Ds_14") (pintype "passive"))
    )
    (net (code "23") (name "/V-5V") (class "Default")
      (node (ref "R135") (pin "1") (pinfunction "1_1") (pintype "passive"))
    )
    (net (code "24") (name "/V-POW1") (class "Default")
      (node (ref "D26") (pin "1") (pinfunction "A_1") (pintype "passive"))
    )
    (net (code "25") (name "/V-POW2") (class "Default")
      (node (ref "D15") (pin "1") (pinfunction "A_1") (pintype "passive"))
    )
    (net (code "26") (name "GND") (class "Default")
      (node (ref "C100") (pin "2") (pinfunction "2_2") (pintype "passive"))
      (node (ref "C102") (pin "1") (pinfunction "1_1") (pintype "passive"))
      (node (ref "C103") (pin "1") (pinfunction "1_1") (pintype "passive"))
      (node (ref "C105") (pin "1") (pinfunction "1_1") (pintype "passive"))
      (node (ref "C107") (pin "1") (pinfunction "1_1") (pintype "passive"))
      (node (ref "C108") (pin "1") (pinfunction "1_1") (pintype "passive"))
      (node (ref "C109") (pin "1") (pinfunction "1_1") (pintype "passive"))
      (node (ref "C110") (pin "2") (pinfunction "2_2") (pintype "passive"))
      (node (ref "C13") (pin "1") (pinfunction "1_1") (pintype "passive"))
      (node (ref "C14") (pin "1") (pinfunction "1_1") (pintype "passive"))
      (node (ref "C15") (pin "2") (pinfunction "2_2") (pintype "passive"))
      (node (ref "C16") (pin "1") (pinfunction "1_1") (pintype "passive"))
      (node (ref "C18") (pin "1") (pinfunction "1_1") (pintype "passive"))
      (node (ref "C2") (pin "1") (pinfunction "1_1") (pintype "passive"))
      (node (ref "C23") (pin "2") (pinfunction "2_2") (pintype "passive"))
      (node (ref "C300") (pin "1") (pinfunction "1_1") (pintype "passive"))
      (node (ref "C32") (pin "1") (pinfunction "1_1") (pintype "passive"))
      (node (ref "C49") (pin "1") (pinfunction "1_1") (pintype "passive"))
      (node (ref "C53") (pin "1") (pinfunction "1_1") (pintype "passive"))
      (node (ref "C54") (pin "2") (pinfunction "2_2") (pintype "passive"))
      (node (ref "C82") (pin "1") (pinfunction "1_1") (pintype "passive"))
      (node (ref "C83") (pin "1") (pinfunction "1_1") (pintype "passive"))
      (node (ref "C84") (pin "1") (pinfunction "1_1") (pintype "passive"))
      (node (ref "C99") (pin "1") (pinfunction "1_1") (pintype "passive"))
      (node (ref "CE1") (pin "2") (pinfunction "2_2") (pintype "passive"))
      (node (ref "CE2") (pin "2") (pinfunction "2_2") (pintype "passive"))
      (node (ref "CE4") (pin "2") (pinfunction "2_2") (pintype "passive"))
      (node (ref "CE5") (pin "2") (pinfunction "2_2") (pintype "passive"))
      (node (ref "CP1") (pin "2") (pinfunction "2_2") (pintype "passive"))
      (node (ref "CP15") (pin "2") (pinfunction "2_2") (pintype "passive"))
      (node (ref "CP19") (pin "2") (pinfunction "2_2") (pintype "passive"))
      (node (ref "CP303") (pin "2") (pinfunction "2_2") (pintype "passive"))
      (node (ref "CP4") (pin "2") (pinfunction "2_2") (pintype "passive"))
      (node (ref "CP5") (pin "2") (pinfunction "2_2") (pintype "passive"))
      (node (ref "CP7") (pin "2") (pinfunction "2_2") (pintype "passive"))
      (node (ref "D10") (pin "2") (pinfunction "2_2") (pintype "passive"))
      (node (ref "D2") (pin "2") (pinfunction "2_2") (pintype "passive"))
      (node (ref "D6") (pin "2") (pinfunction "2_2") (pintype "passive"))
      (node (ref "DW1") (pin "1") (pinfunction "A_1") (pintype "passive"))
      (node (ref "DW300") (pin "1") (pinfunction "A_1") (pintype "passive"))
      (node (ref "DZ15") (pin "2") (pintype "passive"))
      (node (ref "Q11") (pin "2") (pinfunction "E_2") (pintype "passive"))
      (node (ref "Q12") (pin "2") (pinfunction "E_2") (pintype "passive"))
      (node (ref "Q19") (pin "2") (pinfunction "c_2") (pintype "passive"))
      (node (ref "Q20") (pin "2") (pinfunction "gnd_2") (pintype "passive"))
      (node (ref "Q22") (pin "2") (pinfunction "gnd_2") (pintype "passive"))
      (node (ref "Q27") (pin "2") (pinfunction "gnd_2") (pintype "passive"))
      (node (ref "R136") (pin "1") (pinfunction "1_1") (pintype "passive"))
      (node (ref "R161") (pin "1") (pinfunction "1_1") (pintype "passive"))
      (node (ref "R179") (pin "1") (pinfunction "1_1") (pintype "passive"))
      (node (ref "R197") (pin "2") (pinfunction "2_2") (pintype "passive"))
      (node (ref "R45") (pin "1") (pinfunction "1_1") (pintype "passive"))
      (node (ref "R67") (pin "1") (pinfunction "1_1") (pintype "passive"))
      (node (ref "R78") (pin "2") (pinfunction "2_2") (pintype "passive"))
      (node (ref "R79") (pin "2") (pinfunction "2_2") (pintype "passive"))
      (node (ref "U14") (pin "8") (pinfunction "GND_8") (pintype "passive"))
      (node (ref "U22") (pin "8") (pinfunction "GND_8") (pintype "passive"))
      (node (ref "U3") (pin "2") (pinfunction "GND_2") (pintype "passive"))
      (node (ref "U300") (pin "2") (pinfunction "GND_2") (pintype "passive"))
      (node (ref "U4") (pin "3") (pinfunction "GND_3") (pintype "passive"))
      (node (ref "U4") (pin "5") (pinfunction "EN_5") (pintype "passive"))
    )
    (net (code "27") (name "Net-(C51-Pad1)") (class "Default")
      (node (ref "C51") (pin "1") (pinfunction "1_1") (pintype "passive"))
      (node (ref "R194") (pin "2") (pinfunction "2_2") (pintype "passive"))
      (node (ref "R195") (pin "1") (pinfunction "1_1") (pintype "passive"))
      (node (ref "R196") (pin "1") (pinfunction "1_1") (pintype "passive"))
    )
    (net (code "28") (name "Net-(D3-K)") (class "Default")
      (node (ref "D3") (pin "2") (pinfunction "K_2") (pintype "passive"))
      (node (ref "Q20") (pin "1") (pinfunction "in_1") (pintype "input"))
    )
    (net (code "29") (name "Net-(D15-K)") (class "Default")
      (node (ref "D15") (pin "2") (pinfunction "K_2") (pintype "passive"))
      (node (ref "Q27") (pin "1") (pinfunction "in_1") (pintype "input"))
    )
    (net (code "30") (name "Net-(D22-A)") (class "Default")
      (node (ref "C102") (pin "2") (pinfunction "2_2") (pintype "passive"))
      (node (ref "C103") (pin "2") (pinfunction "2_2") (pintype "passive"))
      (node (ref "D22") (pin "1") (pinfunction "A_1") (pintype "passive"))
      (node (ref "L4") (pin "2") (pinfunction "2_2") (pintype "passive"))
      (node (ref "U300") (pin "1") (pinfunction "VIN_1") (pintype "passive"))
    )
    (net (code "31") (name "Net-(D22-K)") (class "Default")
      (node (ref "D22") (pin "2") (pinfunction "K_2") (pintype "passive"))
      (node (ref "R162") (pin "2") (pinfunction "2_2") (pintype "passive"))
    )
    (net (code "32") (name "Net-(D26-K)") (class "Default")
      (node (ref "D26") (pin "2") (pinfunction "K_2") (pintype "passive"))
      (node (ref "Q22") (pin "1") (pinfunction "in_1") (pintype "input"))
    )
    (net (code "33") (name "Net-(DL1-K)") (class "Default")
      (node (ref "DL1") (pin "2") (pinfunction "K_2") (pintype "passive"))
      (node (ref "RL30") (pin "2") (pinfunction "2_2") (pintype "passive"))
    )
    (net (code "34") (name "Net-(DL2-K)") (class "Default")
      (node (ref "DL2") (pin "2") (pinfunction "K_2") (pintype "passive"))
      (node (ref "RL23") (pin "2") (pinfunction "2_2") (pintype "passive"))
    )
    (net (code "35") (name "Net-(DL3-K)") (class "Default")
      (node (ref "DL3") (pin "2") (pinfunction "K_2") (pintype "passive"))
      (node (ref "RL24") (pin "2") (pinfunction "2_2") (pintype "passive"))
    )
    (net (code "36") (name "Net-(DL4-K)") (class "Default")
      (node (ref "DL4") (pin "2") (pinfunction "K_2") (pintype "passive"))
      (node (ref "RL25") (pin "2") (pinfunction "2_2") (pintype "passive"))
    )
    (net (code "37") (name "Net-(DL5-K)") (class "Default")
      (node (ref "DL5") (pin "2") (pinfunction "K_2") (pintype "passive"))
      (node (ref "RL26") (pin "2") (pinfunction "2_2") (pintype "passive"))
    )
    (net (code "38") (name "Net-(DL6-K)") (class "Default")
      (node (ref "DL6") (pin "2") (pinfunction "K_2") (pintype "passive"))
      (node (ref "RL27") (pin "2") (pinfunction "2_2") (pintype "passive"))
    )
    (net (code "39") (name "Net-(DL7-K)") (class "Default")
      (node (ref "DL7") (pin "2") (pinfunction "K_2") (pintype "passive"))
      (node (ref "RL28") (pin "2") (pinfunction "2_2") (pintype "passive"))
    )
    (net (code "40") (name "Net-(DL8-Pad1)") (class "Default")
      (node (ref "DL8") (pin "1") (pinfunction "1_1") (pintype "passive"))
      (node (ref "RL1") (pin "2") (pinfunction "2_2") (pintype "passive"))
    )
    (net (code "41") (name "Net-(DL9-Pad1)") (class "Default")
      (node (ref "DL9") (pin "1") (pinfunction "1_1") (pintype "passive"))
      (node (ref "RL2") (pin "2") (pinfunction "2_2") (pintype "passive"))
    )
    (net (code "42") (name "Net-(DL10-Pad1)") (class "Default")
      (node (ref "DL10") (pin "1") (pinfunction "1_1") (pintype "passive"))
      (node (ref "RL3") (pin "2") (pinfunction "2_2") (pintype "passive"))
    )
    (net (code "43") (name "Net-(DL11-Pad1)") (class "Default")
      (node (ref "DL11") (pin "1") (pinfunction "1_1") (pintype "passive"))
      (node (ref "RL4") (pin "2") (pinfunction "2_2") (pintype "passive"))
    )
    (net (code "44") (name "Net-(DL12-Pad1)") (class "Default")
      (node (ref "DL12") (pin "1") (pinfunction "1_1") (pintype "passive"))
      (node (ref "RL5") (pin "2") (pinfunction "2_2") (pintype "passive"))
    )
    (net (code "45") (name "Net-(DL13-Pad1)") (class "Default")
      (node (ref "DL13") (pin "1") (pinfunction "1_1") (pintype "passive"))
      (node (ref "RL6") (pin "2") (pinfunction "2_2") (pintype "passive"))
    )
    (net (code "46") (name "Net-(DL14-Pad1)") (class "Default")
      (node (ref "DL14") (pin "1") (pinfunction "1_1") (pintype "passive"))
      (node (ref "RL7") (pin "2") (pinfunction "2_2") (pintype "passive"))
    )
    (net (code "47") (name "Net-(DL15-Pad1)") (class "Default")
      (node (ref "DL15") (pin "1") (pinfunction "1_1") (pintype "passive"))
      (node (ref "RL8") (pin "2") (pinfunction "2_2") (pintype "passive"))
    )
    (net (code "48") (name "Net-(DL16-K)") (class "Default")
      (node (ref "DL16") (pin "2") (pinfunction "K_2") (pintype "passive"))
      (node (ref "RL29") (pin "2") (pinfunction "2_2") (pintype "passive"))
    )
    (net (code "49") (name "Net-(DL17-K)") (class "Default")
      (node (ref "DL17") (pin "2") (pinfunction "K_2") (pintype "passive"))
      (node (ref "RL38") (pin "2") (pinfunction "2_2") (pintype "passive"))
    )
    (net (code "50") (name "Net-(DL18-K)") (class "Default")
      (node (ref "DL18") (pin "2") (pinfunction "K_2") (pintype "passive"))
      (node (ref "RL37") (pin "2") (pinfunction "2_2") (pintype "passive"))
    )
    (net (code "51") (name "Net-(DL19-K)") (class "Default")
      (node (ref "DL19") (pin "2") (pinfunction "K_2") (pintype "passive"))
      (node (ref "RL36") (pin "2") (pinfunction "2_2") (pintype "passive"))
    )
    (net (code "52") (name "Net-(DL20-K)") (class "Default")
      (node (ref "DL20") (pin "2") (pinfunction "K_2") (pintype "passive"))
      (node (ref "RL35") (pin "2") (pinfunction "2_2") (pintype "passive"))
    )
    (net (code "53") (name "Net-(DL21-K)") (class "Default")
      (node (ref "DL21") (pin "2") (pinfunction "K_2") (pintype "passive"))
      (node (ref "RL34") (pin "2") (pinfunction "2_2") (pintype "passive"))
    )
    (net (code "54") (name "Net-(DL22-K)") (class "Default")
      (node (ref "DL22") (pin "2") (pinfunction "K_2") (pintype "passive"))
      (node (ref "RL33") (pin "2") (pinfunction "2_2") (pintype "passive"))
    )
    (net (code "55") (name "Net-(DL23-K)") (class "Default")
      (node (ref "DL23") (pin "2") (pinfunction "K_2") (pintype "passive"))
      (node (ref "RL32") (pin "2") (pinfunction "2_2") (pintype "passive"))
    )
    (net (code "56") (name "Net-(DL24-K)") (class "Default")
      (node (ref "DL24") (pin "2") (pinfunction "K_2") (pintype "passive"))
      (node (ref "RL31") (pin "2") (pinfunction "2_2") (pintype "passive"))
    )
    (net (code "57") (name "Net-(DL25-K)") (class "Default")
      (node (ref "DL25") (pin "2") (pinfunction "K_2") (pintype "passive"))
      (node (ref "RL68") (pin "2") (pinfunction "2_2") (pintype "passive"))
    )
    (net (code "58") (name "Net-(DL26-K)") (class "Default")
      (node (ref "DL26") (pin "2") (pinfunction "K_2") (pintype "passive"))
      (node (ref "RL9") (pin "2") (pinfunction "2_2") (pintype "passive"))
    )
    (net (code "59") (name "Net-(DW1-K)") (class "Default")
      (node (ref "DW1") (pin "2") (pinfunction "K_2") (pintype "passive"))
      (node (ref "L2") (pin "1") (pinfunction "1_1") (pintype "passive"))
      (node (ref "U4") (pin "2") (pinfunction "OUT_2") (pintype "passive"))
    )
    (net (code "60") (name "Net-(DW300-K)") (class "Default")
      (node (ref "C19") (pin "1") (pinfunction "1_1") (pintype "passive"))
      (node (ref "DW300") (pin "2") (pinfunction "K_2") (pintype "passive"))
      (node (ref "L302") (pin "1") (pinfunction "1_1") (pintype "passive"))
      (node (ref "U300") (pin "8") (pinfunction "SW_8") (pintype "passive"))
    )
    (net (code "61") (name "Net-(L21-Pad1)") (class "Default")
      (node (ref "L21") (pin "1") (pinfunction "1_1") (pintype "passive"))
      (node (ref "Q21") (pin "2") (pinfunction "D_2") (pintype "passive"))
      (node (ref "Q21") (pin "4") (pinfunction "D_4") (pintype "passive"))
      (node (ref "R133") (pin "2") (pinfunction "2_2") (pintype "passive"))
    )
    (net (code "62") (name "Net-(Q8-Pad1)") (class "Default")
      (node (ref "Q8") (pin "1") (pintype "passive"))
      (node (ref "R171") (pin "1") (pinfunction "1_1") (pintype "passive"))
      (node (ref "R174") (pin "1") (pinfunction "1_1") (pintype "passive"))
    )
    (net (code "63") (name "Net-(Q8-Pad2)") (class "Default")
      (node (ref "Q8") (pin "2") (pintype "passive"))
      (node (ref "R169") (pin "2") (pinfunction "2_2") (pintype "passive"))
      (node (ref "R25") (pin "1") (pinfunction "1_1") (pintype "passive"))
    )
    (net (code "64") (name "Net-(Q11-B)") (class "Default")
      (node (ref "Q11") (pin "1") (pinfunction "B_1") (pintype "input"))
      (node (ref "R75") (pin "2") (pinfunction "2_2") (pintype "passive"))
      (node (ref "R78") (pin "1") (pinfunction "1_1") (pintype "passive"))
    )
    (net (code "65") (name "Net-(Q11-C)") (class "Default")
      (node (ref "DL10") (pin "2") (pinfunction "2_2") (pintype "passive"))
      (node (ref "DL11") (pin "2") (pinfunction "2_2") (pintype "passive"))
      (node (ref "DL8") (pin "2") (pinfunction "2_2") (pintype "passive"))
      (node (ref "DL9") (pin "2") (pinfunction "2_2") (pintype "passive"))
      (node (ref "Q11") (pin "3") (pinfunction "C_3") (pintype "passive"))
    )
    (net (code "66") (name "Net-(Q12-B)") (class "Default")
      (node (ref "Q12") (pin "1") (pinfunction "B_1") (pintype "input"))
      (node (ref "R76") (pin "2") (pinfunction "2_2") (pintype "passive"))
      (node (ref "R79") (pin "1") (pinfunction "1_1") (pintype "passive"))
    )
    (net (code "67") (name "Net-(Q12-C)") (class "Default")
      (node (ref "DL12") (pin "2") (pinfunction "2_2") (pintype "passive"))
      (node (ref "DL13") (pin "2") (pinfunction "2_2") (pintype "passive"))
      (node (ref "DL14") (pin "2") (pinfunction "2_2") (pintype "passive"))
      (node (ref "DL15") (pin "2") (pinfunction "2_2") (pintype "passive"))
      (node (ref "Q12") (pin "3") (pinfunction "C_3") (pintype "passive"))
    )
    (net (code "68") (name "Net-(Q19-b)") (class "Default")
      (node (ref "Q19") (pin "1") (pinfunction "b_1") (pintype "input"))
      (node (ref "R135") (pin "2") (pinfunction "2_2") (pintype "passive"))
      (node (ref "R136") (pin "2") (pinfunction "2_2") (pintype "passive"))
    )
    (net (code "69") (name "Net-(Q19-e)") (class "Default")
      (node (ref "Q19") (pin "3") (pinfunction "e_3") (pintype "passive"))
      (node (ref "Q21") (pin "1") (pinfunction "G_1") (pintype "passive"))
      (node (ref "R134") (pin "2") (pinfunction "2_2") (pintype "passive"))
    )
    (net (code "70") (name "Net-(Q20-out)") (class "Default")
      (node (ref "Q20") (pin "3") (pinfunction "out_3") (pintype "passive"))
      (node (ref "R130") (pin "2") (pinfunction "2_2") (pintype "passive"))
      (node (ref "U300") (pin "3") (pinfunction "EN_3") (pintype "passive"))
    )
    (net (code "71") (name "Net-(Q22-out)") (class "Default")
      (node (ref "Q22") (pin "3") (pinfunction "out_3") (pintype "passive"))
      (node (ref "R174") (pin "2") (pinfunction "2_2") (pintype "passive"))
    )
    (net (code "72") (name "Net-(Q26-Pad1)") (class "Default")
      (node (ref "Q26") (pin "1") (pintype "passive"))
      (node (ref "R102") (pin "1") (pinfunction "1_1") (pintype "passive"))
      (node (ref "R105") (pin "1") (pinfunction "1_1") (pintype "passive"))
    )
    (net (code "73") (name "Net-(Q26-Pad2)") (class "Default")
      (node (ref "Q26") (pin "2") (pintype "passive"))
      (node (ref "R22") (pin "1") (pinfunction "1_1") (pintype "passive"))
      (node (ref "R62") (pin "2") (pinfunction "2_2") (pintype "passive"))
    )
    (net (code "74") (name "Net-(Q27-out)") (class "Default")
      (node (ref "Q27") (pin "3") (pinfunction "out_3") (pintype "passive"))
      (node (ref "R105") (pin "2") (pinfunction "2_2") (pintype "passive"))
    )
    (net (code "75") (name "Net-(R196-Pad2)") (class "Default")
      (node (ref "R196") (pin "2") (pinfunction "2_2") (pintype "passive"))
      (node (ref "R197") (pin "1") (pinfunction "1_1") (pintype "passive"))
    )
    (net (code "76") (name "Net-(U3-VOUT)") (class "Default")
      (node (ref "C100") (pin "1") (pinfunction "1_1") (pintype "passive"))
      (node (ref "CP19") (pin "1") (pinfunction "1_1") (pintype "passive"))
      (node (ref "R178") (pin "1") (pinfunction "1_1") (pintype "passive"))
      (node (ref "U3") (pin "3") (pinfunction "VOUT_3") (pintype "passive"))
    )
    (net (code "77") (name "Net-(U14-D0)") (class "Default")
      (node (ref "RL30") (pin "1") (pinfunction "1_1") (pintype "passive"))
      (node (ref "U14") (pin "15") (pinfunction "D0_15") (pintype "passive"))
    )
    (net (code "78") (name "Net-(U14-D1)") (class "Default")
      (node (ref "RL23") (pin "1") (pinfunction "1_1") (pintype "passive"))
      (node (ref "U14") (pin "1") (pinfunction "D1_1") (pintype "passive"))
    )
    (net (code "79") (name "Net-(U14-D2)") (class "Default")
      (node (ref "RL24") (pin "1") (pinfunction "1_1") (pintype "passive"))
      (node (ref "U14") (pin "2") (pinfunction "D2_2") (pintype "passive"))
    )
    (net (code "80") (name "Net-(U14-D3)") (class "Default")
      (node (ref "RL25") (pin "1") (pinfunction "1_1") (pintype "passive"))
      (node (ref "U14") (pin "3") (pinfunction "D3_3") (pintype "passive"))
    )
    (net (code "81") (name "Net-(U14-D4)") (class "Default")
      (node (ref "RL26") (pin "1") (pinfunction "1_1") (pintype "passive"))
      (node (ref "U14") (pin "4") (pinfunction "D4_4") (pintype "passive"))
    )
    (net (code "82") (name "Net-(U14-D5)") (class "Default")
      (node (ref "RL27") (pin "1") (pinfunction "1_1") (pintype "passive"))
      (node (ref "U14") (pin "5") (pinfunction "D5_5") (pintype "passive"))
    )
    (net (code "83") (name "Net-(U14-D6)") (class "Default")
      (node (ref "RL28") (pin "1") (pinfunction "1_1") (pintype "passive"))
      (node (ref "U14") (pin "6") (pinfunction "D6_6") (pintype "passive"))
    )
    (net (code "84") (name "Net-(U14-D7)") (class "Default")
      (node (ref "RL29") (pin "1") (pinfunction "1_1") (pintype "passive"))
      (node (ref "U14") (pin "7") (pinfunction "D7_7") (pintype "passive"))
    )
    (net (code "85") (name "Net-(U22-D0)") (class "Default")
      (node (ref "RL38") (pin "1") (pinfunction "1_1") (pintype "passive"))
      (node (ref "U22") (pin "15") (pinfunction "D0_15") (pintype "passive"))
    )
    (net (code "86") (name "Net-(U22-D1)") (class "Default")
      (node (ref "RL37") (pin "1") (pinfunction "1_1") (pintype "passive"))
      (node (ref "U22") (pin "1") (pinfunction "D1_1") (pintype "passive"))
    )
    (net (code "87") (name "Net-(U22-D2)") (class "Default")
      (node (ref "RL36") (pin "1") (pinfunction "1_1") (pintype "passive"))
      (node (ref "U22") (pin "2") (pinfunction "D2_2") (pintype "passive"))
    )
    (net (code "88") (name "Net-(U22-D3)") (class "Default")
      (node (ref "RL35") (pin "1") (pinfunction "1_1") (pintype "passive"))
      (node (ref "U22") (pin "3") (pinfunction "D3_3") (pintype "passive"))
    )
    (net (code "89") (name "Net-(U22-D4)") (class "Default")
      (node (ref "RL34") (pin "1") (pinfunction "1_1") (pintype "passive"))
      (node (ref "U22") (pin "4") (pinfunction "D4_4") (pintype "passive"))
    )
    (net (code "90") (name "Net-(U22-D5)") (class "Default")
      (node (ref "RL33") (pin "1") (pinfunction "1_1") (pintype "passive"))
      (node (ref "U22") (pin "5") (pinfunction "D5_5") (pintype "passive"))
    )
    (net (code "91") (name "Net-(U22-D6)") (class "Default")
      (node (ref "RL32") (pin "1") (pinfunction "1_1") (pintype "passive"))
      (node (ref "U22") (pin "6") (pinfunction "D6_6") (pintype "passive"))
    )
    (net (code "92") (name "Net-(U22-D7)") (class "Default")
      (node (ref "RL31") (pin "1") (pinfunction "1_1") (pintype "passive"))
      (node (ref "U22") (pin "7") (pinfunction "D7_7") (pintype "passive"))
    )
    (net (code "93") (name "Net-(U300-BST)") (class "Default")
      (node (ref "C19") (pin "2") (pinfunction "2_2") (pintype "passive"))
      (node (ref "R162") (pin "1") (pinfunction "1_1") (pintype "passive"))
      (node (ref "U300") (pin "7") (pinfunction "BST_7") (pintype "passive"))
    )
    (net (code "94") (name "Net-(U300-FB)") (class "Default")
      (node (ref "R195") (pin "2") (pinfunction "2_2") (pintype "passive"))
      (node (ref "U300") (pin "4") (pinfunction "FB_4") (pintype "passive"))
    )
    (net (code "95") (name "Net-(U300-SS)") (class "Default")
      (node (ref "C49") (pin "2") (pinfunction "2_2") (pintype "passive"))
      (node (ref "U300") (pin "5") (pinfunction "SS_5") (pintype "passive"))
    )
    (net (code "96") (name "Net-(U300-VO)") (class "Default")
      (node (ref "R163") (pin "1") (pinfunction "1_1") (pintype "passive"))
      (node (ref "R179") (pin "2") (pinfunction "2_2") (pintype "passive"))
      (node (ref "U300") (pin "6") (pinfunction "VO_6") (pintype "passive"))
    )
    (net (code "97") (name "V") (class "Default")
      (node (ref "C107") (pin "2") (pinfunction "2_2") (pintype "passive"))
      (node (ref "C108") (pin "2") (pinfunction "2_2") (pintype "passive"))
      (node (ref "C14") (pin "2") (pinfunction "2_2") (pintype "passive"))
      (node (ref "C2") (pin "2") (pinfunction "2_2") (pintype "passive"))
      (node (ref "C300") (pin "2") (pinfunction "2_2") (pintype "passive"))
      (node (ref "C83") (pin "2") (pinfunction "2_2") (pintype "passive"))
      (node (ref "CP1") (pin "1") (pinfunction "1_1") (pintype "passive"))
      (node (ref "CP15") (pin "1") (pinfunction "1_1") (pintype "passive"))
      (node (ref "D2") (pin "1") (pinfunction "1_1") (pintype "passive"))
      (node (ref "D7") (pin "2") (pinfunction "K_2") (pintype "passive"))
      (node (ref "L1") (pin "1") (pinfunction "1_1") (pintype "passive"))
      (node (ref "L4") (pin "1") (pinfunction "1_1") (pintype "passive"))
      (node (ref "R176") (pin "1") (pinfunction "1_1") (pintype "passive"))
    )
    (net (code "98") (name "unconnected-(DZ15-Pad5)") (class "Default")
      (node (ref "DZ15") (pin "5") (pintype "passive"))
    )
    (net (code "99") (name "unconnected-(DZ15-Pad6)") (class "Default")
      (node (ref "DZ15") (pin "6") (pintype "passive"))
    )
    (net (code "100") (name "unconnected-(TP1-Pad1)") (class "Default")
      (node (ref "TP1") (pin "1") (pinfunction "1_1") (pintype "passive"))
    )
    (net (code "101") (name "unconnected-(TP2-Pad1)") (class "Default")
      (node (ref "TP2") (pin "1") (pinfunction "1_1") (pintype "passive"))
    )
    (net (code "102") (name "unconnected-(TP3-Pad1)") (class "Default")
      (node (ref "TP3") (pin "1") (pinfunction "1_1") (pintype "passive"))
    )
    (net (code "103") (name "unconnected-(TP4-Pad1)") (class "Default")
      (node (ref "TP4") (pin "1") (pinfunction "1_1") (pintype "passive"))
    )
    (net (code "104") (name "unconnected-(U14-D7`-Pad9)") (class "Default")
      (node (ref "U14") (pin "9") (pinfunction "D7`_9") (pintype "passive"))
    )
    (net (code "105") (name "unconnected-(U22-D7`-Pad9)") (class "Default")
      (node (ref "U22") (pin "9") (pinfunction "D7`_9") (pintype "passive"))
    )
  )
)
